# Bonus.net
KiCad netlist of a schematic drawn in EAGLE
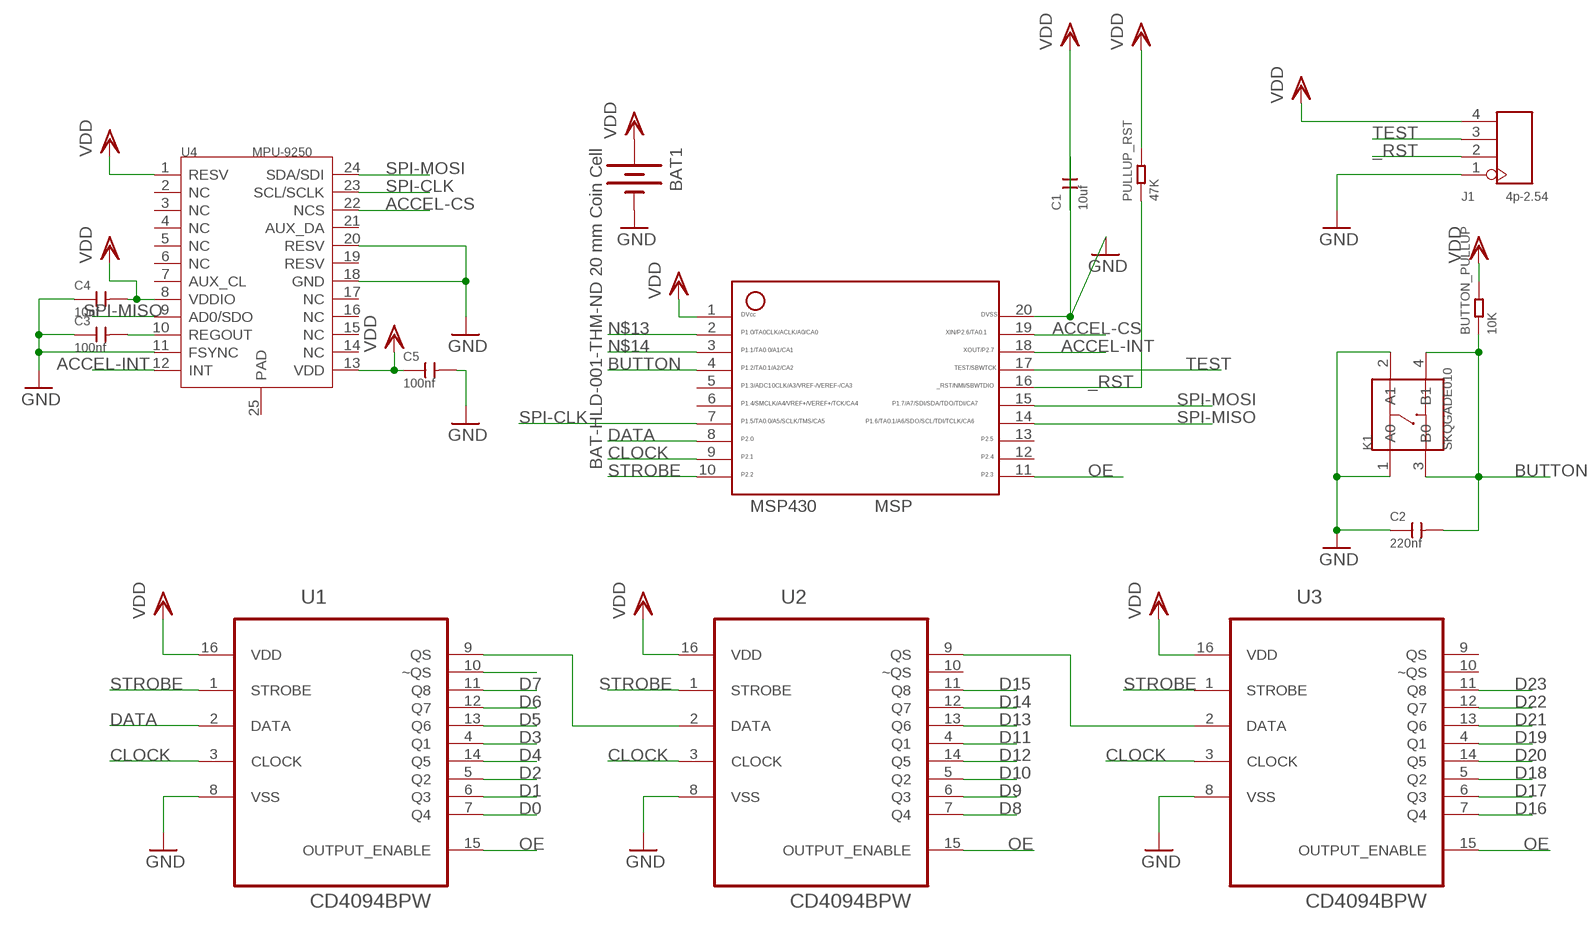
[diagram p0: schematic, sheet 1]
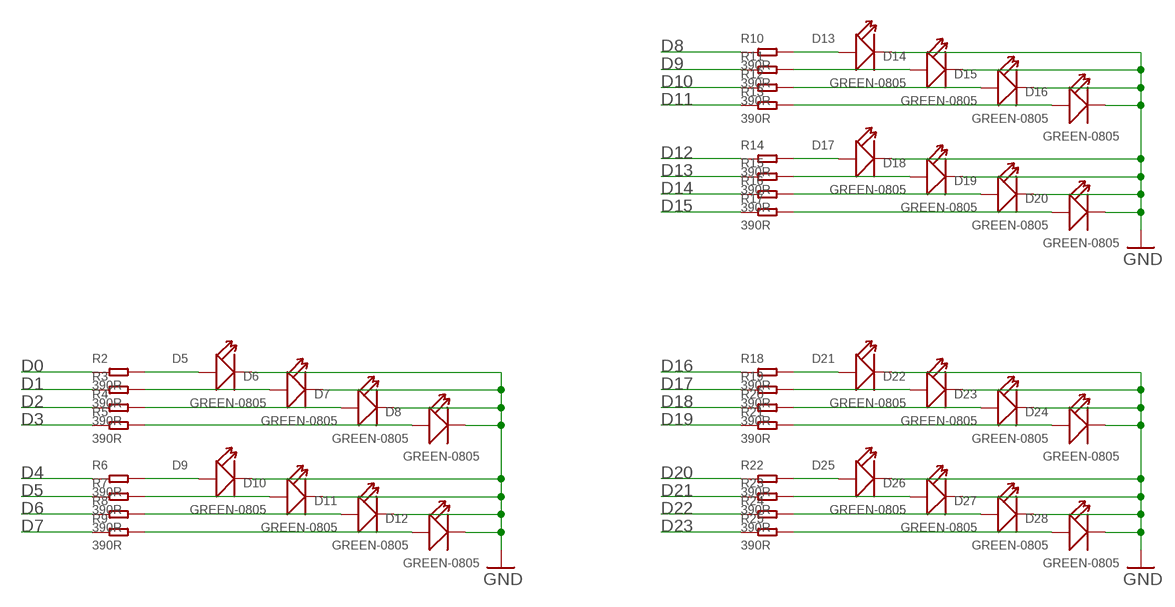
[diagram p1: schematic, sheet 2]

(export (version "E")
  (design (tool "Eeschema 10.0.6"))
  (components
    (comp (ref "D5")
      (value "GREEN-0805")
      (footprint "eagle-import:LED-0805")
      (fields (field (name "MPN") "17-215SYGC/S530-E2/TR8"))
      (libsource (lib "eagle-import") (part "SMD-LED-CLEAR-GREEN(0805)"))
    )
    (comp (ref "D6")
      (value "GREEN-0805")
      (footprint "eagle-import:LED-0805")
      (fields (field (name "MPN") "17-215SYGC/S530-E2/TR8"))
      (libsource (lib "eagle-import") (part "SMD-LED-CLEAR-GREEN(0805)"))
    )
    (comp (ref "D7")
      (value "GREEN-0805")
      (footprint "eagle-import:LED-0805")
      (fields (field (name "MPN") "17-215SYGC/S530-E2/TR8"))
      (libsource (lib "eagle-import") (part "SMD-LED-CLEAR-GREEN(0805)"))
    )
    (comp (ref "D8")
      (value "GREEN-0805")
      (footprint "eagle-import:LED-0805")
      (fields (field (name "MPN") "17-215SYGC/S530-E2/TR8"))
      (libsource (lib "eagle-import") (part "SMD-LED-CLEAR-GREEN(0805)"))
    )
    (comp (ref "D9")
      (value "GREEN-0805")
      (footprint "eagle-import:LED-0805")
      (fields (field (name "MPN") "17-215SYGC/S530-E2/TR8"))
      (libsource (lib "eagle-import") (part "SMD-LED-CLEAR-GREEN(0805)"))
    )
    (comp (ref "D10")
      (value "GREEN-0805")
      (footprint "eagle-import:LED-0805")
      (fields (field (name "MPN") "17-215SYGC/S530-E2/TR8"))
      (libsource (lib "eagle-import") (part "SMD-LED-CLEAR-GREEN(0805)"))
    )
    (comp (ref "D11")
      (value "GREEN-0805")
      (footprint "eagle-import:LED-0805")
      (fields (field (name "MPN") "17-215SYGC/S530-E2/TR8"))
      (libsource (lib "eagle-import") (part "SMD-LED-CLEAR-GREEN(0805)"))
    )
    (comp (ref "D12")
      (value "GREEN-0805")
      (footprint "eagle-import:LED-0805")
      (fields (field (name "MPN") "17-215SYGC/S530-E2/TR8"))
      (libsource (lib "eagle-import") (part "SMD-LED-CLEAR-GREEN(0805)"))
    )
    (comp (ref "D13")
      (value "GREEN-0805")
      (footprint "eagle-import:LED-0805")
      (fields (field (name "MPN") "17-215SYGC/S530-E2/TR8"))
      (libsource (lib "eagle-import") (part "SMD-LED-CLEAR-GREEN(0805)"))
    )
    (comp (ref "D14")
      (value "GREEN-0805")
      (footprint "eagle-import:LED-0805")
      (fields (field (name "MPN") "17-215SYGC/S530-E2/TR8"))
      (libsource (lib "eagle-import") (part "SMD-LED-CLEAR-GREEN(0805)"))
    )
    (comp (ref "D15")
      (value "GREEN-0805")
      (footprint "eagle-import:LED-0805")
      (fields (field (name "MPN") "17-215SYGC/S530-E2/TR8"))
      (libsource (lib "eagle-import") (part "SMD-LED-CLEAR-GREEN(0805)"))
    )
    (comp (ref "D16")
      (value "GREEN-0805")
      (footprint "eagle-import:LED-0805")
      (fields (field (name "MPN") "17-215SYGC/S530-E2/TR8"))
      (libsource (lib "eagle-import") (part "SMD-LED-CLEAR-GREEN(0805)"))
    )
    (comp (ref "D17")
      (value "GREEN-0805")
      (footprint "eagle-import:LED-0805")
      (fields (field (name "MPN") "17-215SYGC/S530-E2/TR8"))
      (libsource (lib "eagle-import") (part "SMD-LED-CLEAR-GREEN(0805)"))
    )
    (comp (ref "D18")
      (value "GREEN-0805")
      (footprint "eagle-import:LED-0805")
      (fields (field (name "MPN") "17-215SYGC/S530-E2/TR8"))
      (libsource (lib "eagle-import") (part "SMD-LED-CLEAR-GREEN(0805)"))
    )
    (comp (ref "D19")
      (value "GREEN-0805")
      (footprint "eagle-import:LED-0805")
      (fields (field (name "MPN") "17-215SYGC/S530-E2/TR8"))
      (libsource (lib "eagle-import") (part "SMD-LED-CLEAR-GREEN(0805)"))
    )
    (comp (ref "D20")
      (value "GREEN-0805")
      (footprint "eagle-import:LED-0805")
      (fields (field (name "MPN") "17-215SYGC/S530-E2/TR8"))
      (libsource (lib "eagle-import") (part "SMD-LED-CLEAR-GREEN(0805)"))
    )
    (comp (ref "D21")
      (value "GREEN-0805")
      (footprint "eagle-import:LED-0805")
      (fields (field (name "MPN") "17-215SYGC/S530-E2/TR8"))
      (libsource (lib "eagle-import") (part "SMD-LED-CLEAR-GREEN(0805)"))
    )
    (comp (ref "D22")
      (value "GREEN-0805")
      (footprint "eagle-import:LED-0805")
      (fields (field (name "MPN") "17-215SYGC/S530-E2/TR8"))
      (libsource (lib "eagle-import") (part "SMD-LED-CLEAR-GREEN(0805)"))
    )
    (comp (ref "D23")
      (value "GREEN-0805")
      (footprint "eagle-import:LED-0805")
      (fields (field (name "MPN") "17-215SYGC/S530-E2/TR8"))
      (libsource (lib "eagle-import") (part "SMD-LED-CLEAR-GREEN(0805)"))
    )
    (comp (ref "D24")
      (value "GREEN-0805")
      (footprint "eagle-import:LED-0805")
      (fields (field (name "MPN") "17-215SYGC/S530-E2/TR8"))
      (libsource (lib "eagle-import") (part "SMD-LED-CLEAR-GREEN(0805)"))
    )
    (comp (ref "D25")
      (value "GREEN-0805")
      (footprint "eagle-import:LED-0805")
      (fields (field (name "MPN") "17-215SYGC/S530-E2/TR8"))
      (libsource (lib "eagle-import") (part "SMD-LED-CLEAR-GREEN(0805)"))
    )
    (comp (ref "D26")
      (value "GREEN-0805")
      (footprint "eagle-import:LED-0805")
      (fields (field (name "MPN") "17-215SYGC/S530-E2/TR8"))
      (libsource (lib "eagle-import") (part "SMD-LED-CLEAR-GREEN(0805)"))
    )
    (comp (ref "D27")
      (value "GREEN-0805")
      (footprint "eagle-import:LED-0805")
      (fields (field (name "MPN") "17-215SYGC/S530-E2/TR8"))
      (libsource (lib "eagle-import") (part "SMD-LED-CLEAR-GREEN(0805)"))
    )
    (comp (ref "D28")
      (value "GREEN-0805")
      (footprint "eagle-import:LED-0805")
      (fields (field (name "MPN") "17-215SYGC/S530-E2/TR8"))
      (libsource (lib "eagle-import") (part "SMD-LED-CLEAR-GREEN(0805)"))
    )
    (comp (ref "R2")
      (value "390R")
      (footprint "eagle-import:R0603")
      (fields (field (name "MPN") "RC0603JR-07390RL"))
      (libsource (lib "eagle-import") (part "SMD-RES-390R-5%-1/10W(0603)"))
    )
    (comp (ref "R3")
      (value "390R")
      (footprint "eagle-import:R0603")
      (fields (field (name "MPN") "RC0603JR-07390RL"))
      (libsource (lib "eagle-import") (part "SMD-RES-390R-5%-1/10W(0603)"))
    )
    (comp (ref "R4")
      (value "390R")
      (footprint "eagle-import:R0603")
      (fields (field (name "MPN") "RC0603JR-07390RL"))
      (libsource (lib "eagle-import") (part "SMD-RES-390R-5%-1/10W(0603)"))
    )
    (comp (ref "R5")
      (value "390R")
      (footprint "eagle-import:R0603")
      (fields (field (name "MPN") "RC0603JR-07390RL"))
      (libsource (lib "eagle-import") (part "SMD-RES-390R-5%-1/10W(0603)"))
    )
    (comp (ref "R6")
      (value "390R")
      (footprint "eagle-import:R0603")
      (fields (field (name "MPN") "RC0603JR-07390RL"))
      (libsource (lib "eagle-import") (part "SMD-RES-390R-5%-1/10W(0603)"))
    )
    (comp (ref "R7")
      (value "390R")
      (footprint "eagle-import:R0603")
      (fields (field (name "MPN") "RC0603JR-07390RL"))
      (libsource (lib "eagle-import") (part "SMD-RES-390R-5%-1/10W(0603)"))
    )
    (comp (ref "R8")
      (value "390R")
      (footprint "eagle-import:R0603")
      (fields (field (name "MPN") "RC0603JR-07390RL"))
      (libsource (lib "eagle-import") (part "SMD-RES-390R-5%-1/10W(0603)"))
    )
    (comp (ref "R9")
      (value "390R")
      (footprint "eagle-import:R0603")
      (fields (field (name "MPN") "RC0603JR-07390RL"))
      (libsource (lib "eagle-import") (part "SMD-RES-390R-5%-1/10W(0603)"))
    )
    (comp (ref "R10")
      (value "390R")
      (footprint "eagle-import:R0603")
      (fields (field (name "MPN") "RC0603JR-07390RL"))
      (libsource (lib "eagle-import") (part "SMD-RES-390R-5%-1/10W(0603)"))
    )
    (comp (ref "R11")
      (value "390R")
      (footprint "eagle-import:R0603")
      (fields (field (name "MPN") "RC0603JR-07390RL"))
      (libsource (lib "eagle-import") (part "SMD-RES-390R-5%-1/10W(0603)"))
    )
    (comp (ref "R12")
      (value "390R")
      (footprint "eagle-import:R0603")
      (fields (field (name "MPN") "RC0603JR-07390RL"))
      (libsource (lib "eagle-import") (part "SMD-RES-390R-5%-1/10W(0603)"))
    )
    (comp (ref "R13")
      (value "390R")
      (footprint "eagle-import:R0603")
      (fields (field (name "MPN") "RC0603JR-07390RL"))
      (libsource (lib "eagle-import") (part "SMD-RES-390R-5%-1/10W(0603)"))
    )
    (comp (ref "R14")
      (value "390R")
      (footprint "eagle-import:R0603")
      (fields (field (name "MPN") "RC0603JR-07390RL"))
      (libsource (lib "eagle-import") (part "SMD-RES-390R-5%-1/10W(0603)"))
    )
    (comp (ref "R15")
      (value "390R")
      (footprint "eagle-import:R0603")
      (fields (field (name "MPN") "RC0603JR-07390RL"))
      (libsource (lib "eagle-import") (part "SMD-RES-390R-5%-1/10W(0603)"))
    )
    (comp (ref "R16")
      (value "390R")
      (footprint "eagle-import:R0603")
      (fields (field (name "MPN") "RC0603JR-07390RL"))
      (libsource (lib "eagle-import") (part "SMD-RES-390R-5%-1/10W(0603)"))
    )
    (comp (ref "R17")
      (value "390R")
      (footprint "eagle-import:R0603")
      (fields (field (name "MPN") "RC0603JR-07390RL"))
      (libsource (lib "eagle-import") (part "SMD-RES-390R-5%-1/10W(0603)"))
    )
    (comp (ref "R18")
      (value "390R")
      (footprint "eagle-import:R0603")
      (fields (field (name "MPN") "RC0603JR-07390RL"))
      (libsource (lib "eagle-import") (part "SMD-RES-390R-5%-1/10W(0603)"))
    )
    (comp (ref "R19")
      (value "390R")
      (footprint "eagle-import:R0603")
      (fields (field (name "MPN") "RC0603JR-07390RL"))
      (libsource (lib "eagle-import") (part "SMD-RES-390R-5%-1/10W(0603)"))
    )
    (comp (ref "R20")
      (value "390R")
      (footprint "eagle-import:R0603")
      (fields (field (name "MPN") "RC0603JR-07390RL"))
      (libsource (lib "eagle-import") (part "SMD-RES-390R-5%-1/10W(0603)"))
    )
    (comp (ref "R21")
      (value "390R")
      (footprint "eagle-import:R0603")
      (fields (field (name "MPN") "RC0603JR-07390RL"))
      (libsource (lib "eagle-import") (part "SMD-RES-390R-5%-1/10W(0603)"))
    )
    (comp (ref "R22")
      (value "390R")
      (footprint "eagle-import:R0603")
      (fields (field (name "MPN") "RC0603JR-07390RL"))
      (libsource (lib "eagle-import") (part "SMD-RES-390R-5%-1/10W(0603)"))
    )
    (comp (ref "R23")
      (value "390R")
      (footprint "eagle-import:R0603")
      (fields (field (name "MPN") "RC0603JR-07390RL"))
      (libsource (lib "eagle-import") (part "SMD-RES-390R-5%-1/10W(0603)"))
    )
    (comp (ref "R24")
      (value "390R")
      (footprint "eagle-import:R0603")
      (fields (field (name "MPN") "RC0603JR-07390RL"))
      (libsource (lib "eagle-import") (part "SMD-RES-390R-5%-1/10W(0603)"))
    )
    (comp (ref "R25")
      (value "390R")
      (footprint "eagle-import:R0603")
      (fields (field (name "MPN") "RC0603JR-07390RL"))
      (libsource (lib "eagle-import") (part "SMD-RES-390R-5%-1/10W(0603)"))
    )
    (comp (ref "BAT1")
      (value "BAT-HLD-001-THM-ND 20 mm Coin Cell")
      (footprint "eagle-import:BATTCON_20MM_PTH_COMPACT")
      (libsource (lib "eagle-import") (part "BATTERYFOB"))
    )
    (comp (ref "BUTTON_PULLUP")
      (value "10K")
      (footprint "eagle-import:R0603")
      (fields (field (name "MPN") "RC0603FR-0710KL"))
      (libsource (lib "eagle-import") (part "SMD-RES-10K-1%-1/10W(0603)"))
    )
    (comp (ref "C1")
      (value "10uf")
      (footprint "eagle-import:C0805")
      (fields (field (name "MPN") "CC0805ZKY5V6BB106"))
      (libsource (lib "eagle-import") (part "CERAMIC-10UF-10V-(-20%～+80%)-Y5V(0805)"))
    )
    (comp (ref "C2")
      (value "220nf")
      (footprint "eagle-import:C0603")
      (fields (field (name "MPN") "CC0603KRX7R8BB224"))
      (libsource (lib "eagle-import") (part "CERAMIC-220NF-25V-10%-X7R(0603)"))
    )
    (comp (ref "C3")
      (value "100nf")
      (footprint "eagle-import:C0402")
      (fields (field (name "MPN") "CC0402KRX7R8BB104"))
      (libsource (lib "eagle-import") (part "CERAMIC-100NF-25V-10%-X7R(0402)"))
    )
    (comp (ref "C4")
      (value "10nf")
      (footprint "eagle-import:C0402")
      (fields (field (name "MPN") "CC0402KRX7R9BB103"))
      (libsource (lib "eagle-import") (part "CERAMIC-10NF-50V-10%-X7R(0402)"))
    )
    (comp (ref "C5")
      (value "100nf")
      (footprint "eagle-import:C0402")
      (fields (field (name "MPN") "CC0402KRX7R8BB104"))
      (libsource (lib "eagle-import") (part "CERAMIC-100NF-25V-10%-X7R(0402)"))
    )
    (comp (ref "J1")
      (value "4p-2.54")
      (footprint "eagle-import:H4-2.54")
      (fields (field (name "MPN") "F185-1104A1BSYA1"))
      (libsource (lib "eagle-import") (part "DIP-BLACK-FEMALE-HEADER-VERT(4P-2.54)"))
    )
    (comp (ref "K1")
      (value "SKQGADE010")
      (footprint "eagle-import:SW4-SMD-5.2X5.2X1.5MM")
      (libsource (lib "eagle-import") (part "SMD-BUTTON(4P-5.2X5.2X1.5MM-SKQGADE010)-SKQGADE010"))
    )
    (comp (ref "MSP430")
      (value "MSP")
      (footprint "eagle-import:20_PIN")
      (libsource (lib "eagle-import") (part "MSP430"))
    )
    (comp (ref "PULLUP_RST")
      (value "47K")
      (footprint "eagle-import:R0603")
      (fields (field (name "MPN") "RC0603JR-0747KL"))
      (libsource (lib "eagle-import") (part "SMD-RES-47K-5%-1/10W(0603)"))
    )
    (comp (ref "U1")
      (value "CD4094BPW")
      (footprint "eagle-import:SOP65P640X120-16N")
      (libsource (lib "eagle-import") (part "CD4094BPW"))
    )
    (comp (ref "U2")
      (value "CD4094BPW")
      (footprint "eagle-import:SOP65P640X120-16N")
      (libsource (lib "eagle-import") (part "CD4094BPW"))
    )
    (comp (ref "U3")
      (value "CD4094BPW")
      (footprint "eagle-import:SOP65P640X120-16N")
      (libsource (lib "eagle-import") (part "CD4094BPW"))
    )
    (comp (ref "U4")
      (value "MPU-9250")
      (footprint "eagle-import:QFN24G-0.4-3X3MM")
      (libsource (lib "eagle-import") (part "MOTION/POSITION-MPU-9250(QFN24)"))
    )
  )
  (nets
    (net (code "1") (name "ACCEL-CS") (class "Default")
      (node (ref "MSP430") (pin "19") (pinfunction "19_19") (pintype "bidirectional"))
      (node (ref "U4") (pin "22") (pinfunction "NCS_22") (pintype "bidirectional"))
    )
    (net (code "2") (name "ACCEL-INT") (class "Default")
      (node (ref "MSP430") (pin "18") (pinfunction "18_18") (pintype "bidirectional"))
      (node (ref "U4") (pin "12") (pinfunction "INT_12") (pintype "bidirectional"))
    )
    (net (code "3") (name "BUTTON") (class "Default")
      (node (ref "BUTTON_PULLUP") (pin "1") (pinfunction "1_1") (pintype "passive"))
      (node (ref "C2") (pin "2") (pinfunction "2_2") (pintype "passive"))
      (node (ref "K1") (pin "3") (pinfunction "B0_3") (pintype "bidirectional"))
      (node (ref "K1") (pin "4") (pinfunction "B1_4") (pintype "bidirectional"))
      (node (ref "MSP430") (pin "4") (pinfunction "4_4") (pintype "bidirectional"))
    )
    (net (code "4") (name "CLOCK") (class "Default")
      (node (ref "MSP430") (pin "9") (pinfunction "9_9") (pintype "bidirectional"))
      (node (ref "U1") (pin "3") (pinfunction "CLOCK_3") (pintype "input"))
      (node (ref "U2") (pin "3") (pinfunction "CLOCK_3") (pintype "input"))
      (node (ref "U3") (pin "3") (pinfunction "CLOCK_3") (pintype "input"))
    )
    (net (code "5") (name "D0") (class "Default")
      (node (ref "R2") (pin "1") (pinfunction "1_1") (pintype "passive"))
      (node (ref "U1") (pin "7") (pinfunction "Q4_7") (pintype "output"))
    )
    (net (code "6") (name "D1") (class "Default")
      (node (ref "R3") (pin "1") (pinfunction "1_1") (pintype "passive"))
      (node (ref "U1") (pin "6") (pinfunction "Q3_6") (pintype "output"))
    )
    (net (code "7") (name "D2") (class "Default")
      (node (ref "R4") (pin "1") (pinfunction "1_1") (pintype "passive"))
      (node (ref "U1") (pin "5") (pinfunction "Q2_5") (pintype "output"))
    )
    (net (code "8") (name "D3") (class "Default")
      (node (ref "R5") (pin "1") (pinfunction "1_1") (pintype "passive"))
      (node (ref "U1") (pin "4") (pinfunction "Q1_4") (pintype "output"))
    )
    (net (code "9") (name "D4") (class "Default")
      (node (ref "R6") (pin "1") (pinfunction "1_1") (pintype "passive"))
      (node (ref "U1") (pin "14") (pinfunction "Q5_14") (pintype "output"))
    )
    (net (code "10") (name "D5") (class "Default")
      (node (ref "R7") (pin "1") (pinfunction "1_1") (pintype "passive"))
      (node (ref "U1") (pin "13") (pinfunction "Q6_13") (pintype "output"))
    )
    (net (code "11") (name "D6") (class "Default")
      (node (ref "R8") (pin "1") (pinfunction "1_1") (pintype "passive"))
      (node (ref "U1") (pin "12") (pinfunction "Q7_12") (pintype "output"))
    )
    (net (code "12") (name "D7") (class "Default")
      (node (ref "R9") (pin "1") (pinfunction "1_1") (pintype "passive"))
      (node (ref "U1") (pin "11") (pinfunction "Q8_11") (pintype "output"))
    )
    (net (code "13") (name "D8") (class "Default")
      (node (ref "R10") (pin "1") (pinfunction "1_1") (pintype "passive"))
      (node (ref "U2") (pin "7") (pinfunction "Q4_7") (pintype "output"))
    )
    (net (code "14") (name "D9") (class "Default")
      (node (ref "R11") (pin "1") (pinfunction "1_1") (pintype "passive"))
      (node (ref "U2") (pin "6") (pinfunction "Q3_6") (pintype "output"))
    )
    (net (code "15") (name "D10") (class "Default")
      (node (ref "R12") (pin "1") (pinfunction "1_1") (pintype "passive"))
      (node (ref "U2") (pin "5") (pinfunction "Q2_5") (pintype "output"))
    )
    (net (code "16") (name "D11") (class "Default")
      (node (ref "R13") (pin "1") (pinfunction "1_1") (pintype "passive"))
      (node (ref "U2") (pin "4") (pinfunction "Q1_4") (pintype "output"))
    )
    (net (code "17") (name "D12") (class "Default")
      (node (ref "R14") (pin "1") (pinfunction "1_1") (pintype "passive"))
      (node (ref "U2") (pin "14") (pinfunction "Q5_14") (pintype "output"))
    )
    (net (code "18") (name "D13") (class "Default")
      (node (ref "R15") (pin "1") (pinfunction "1_1") (pintype "passive"))
      (node (ref "U2") (pin "13") (pinfunction "Q6_13") (pintype "output"))
    )
    (net (code "19") (name "D14") (class "Default")
      (node (ref "R16") (pin "1") (pinfunction "1_1") (pintype "passive"))
      (node (ref "U2") (pin "12") (pinfunction "Q7_12") (pintype "output"))
    )
    (net (code "20") (name "D15") (class "Default")
      (node (ref "R17") (pin "1") (pinfunction "1_1") (pintype "passive"))
      (node (ref "U2") (pin "11") (pinfunction "Q8_11") (pintype "output"))
    )
    (net (code "21") (name "D16") (class "Default")
      (node (ref "R18") (pin "1") (pinfunction "1_1") (pintype "passive"))
      (node (ref "U3") (pin "7") (pinfunction "Q4_7") (pintype "output"))
    )
    (net (code "22") (name "D17") (class "Default")
      (node (ref "R19") (pin "1") (pinfunction "1_1") (pintype "passive"))
      (node (ref "U3") (pin "6") (pinfunction "Q3_6") (pintype "output"))
    )
    (net (code "23") (name "D18") (class "Default")
      (node (ref "R20") (pin "1") (pinfunction "1_1") (pintype "passive"))
      (node (ref "U3") (pin "5") (pinfunction "Q2_5") (pintype "output"))
    )
    (net (code "24") (name "D19") (class "Default")
      (node (ref "R21") (pin "1") (pinfunction "1_1") (pintype "passive"))
      (node (ref "U3") (pin "4") (pinfunction "Q1_4") (pintype "output"))
    )
    (net (code "25") (name "D20") (class "Default")
      (node (ref "R22") (pin "1") (pinfunction "1_1") (pintype "passive"))
      (node (ref "U3") (pin "14") (pinfunction "Q5_14") (pintype "output"))
    )
    (net (code "26") (name "D21") (class "Default")
      (node (ref "R23") (pin "1") (pinfunction "1_1") (pintype "passive"))
      (node (ref "U3") (pin "13") (pinfunction "Q6_13") (pintype "output"))
    )
    (net (code "27") (name "D22") (class "Default")
      (node (ref "R24") (pin "1") (pinfunction "1_1") (pintype "passive"))
      (node (ref "U3") (pin "12") (pinfunction "Q7_12") (pintype "output"))
    )
    (net (code "28") (name "D23") (class "Default")
      (node (ref "R25") (pin "1") (pinfunction "1_1") (pintype "passive"))
      (node (ref "U3") (pin "11") (pinfunction "Q8_11") (pintype "output"))
    )
    (net (code "29") (name "DATA") (class "Default")
      (node (ref "MSP430") (pin "8") (pinfunction "8_8") (pintype "bidirectional"))
      (node (ref "U1") (pin "2") (pinfunction "DATA_2") (pintype "input"))
    )
    (net (code "30") (name "GND") (class "Default")
      (node (ref "BAT1") (pin "2") (pinfunction "-_2") (pintype "power_in"))
      (node (ref "C1") (pin "2") (pinfunction "2_2") (pintype "passive"))
      (node (ref "C2") (pin "1") (pinfunction "1_1") (pintype "passive"))
      (node (ref "C3") (pin "1") (pinfunction "1_1") (pintype "passive"))
      (node (ref "C4") (pin "1") (pinfunction "1_1") (pintype "passive"))
      (node (ref "C5") (pin "2") (pinfunction "2_2") (pintype "passive"))
      (node (ref "D10") (pin "-") (pinfunction "-_-") (pintype "passive"))
      (node (ref "D11") (pin "-") (pinfunction "-_-") (pintype "passive"))
      (node (ref "D12") (pin "-") (pinfunction "-_-") (pintype "passive"))
      (node (ref "D13") (pin "-") (pinfunction "-_-") (pintype "passive"))
      (node (ref "D14") (pin "-") (pinfunction "-_-") (pintype "passive"))
      (node (ref "D15") (pin "-") (pinfunction "-_-") (pintype "passive"))
      (node (ref "D16") (pin "-") (pinfunction "-_-") (pintype "passive"))
      (node (ref "D17") (pin "-") (pinfunction "-_-") (pintype "passive"))
      (node (ref "D18") (pin "-") (pinfunction "-_-") (pintype "passive"))
      (node (ref "D19") (pin "-") (pinfunction "-_-") (pintype "passive"))
      (node (ref "D20") (pin "-") (pinfunction "-_-") (pintype "passive"))
      (node (ref "D21") (pin "-") (pinfunction "-_-") (pintype "passive"))
      (node (ref "D22") (pin "-") (pinfunction "-_-") (pintype "passive"))
      (node (ref "D23") (pin "-") (pinfunction "-_-") (pintype "passive"))
      (node (ref "D24") (pin "-") (pinfunction "-_-") (pintype "passive"))
      (node (ref "D25") (pin "-") (pinfunction "-_-") (pintype "passive"))
      (node (ref "D26") (pin "-") (pinfunction "-_-") (pintype "passive"))
      (node (ref "D27") (pin "-") (pinfunction "-_-") (pintype "passive"))
      (node (ref "D28") (pin "-") (pinfunction "-_-") (pintype "passive"))
      (node (ref "D5") (pin "-") (pinfunction "-_-") (pintype "passive"))
      (node (ref "D6") (pin "-") (pinfunction "-_-") (pintype "passive"))
      (node (ref "D7") (pin "-") (pinfunction "-_-") (pintype "passive"))
      (node (ref "D8") (pin "-") (pinfunction "-_-") (pintype "passive"))
      (node (ref "D9") (pin "-") (pinfunction "-_-") (pintype "passive"))
      (node (ref "J1") (pin "1") (pinfunction "P$1_1") (pintype "bidirectional"))
      (node (ref "K1") (pin "1") (pinfunction "A0_1") (pintype "bidirectional"))
      (node (ref "K1") (pin "2") (pinfunction "A1_2") (pintype "bidirectional"))
      (node (ref "MSP430") (pin "20") (pinfunction "20_20") (pintype "bidirectional"))
      (node (ref "U1") (pin "8") (pinfunction "VSS_8") (pintype "power_in"))
      (node (ref "U2") (pin "8") (pinfunction "VSS_8") (pintype "power_in"))
      (node (ref "U3") (pin "8") (pinfunction "VSS_8") (pintype "power_in"))
      (node (ref "U4") (pin "11") (pinfunction "FSYNC_11") (pintype "bidirectional"))
      (node (ref "U4") (pin "18") (pinfunction "GND_18") (pintype "bidirectional"))
      (node (ref "U4") (pin "20") (pinfunction "RESV_20") (pintype "bidirectional"))
    )
    (net (code "31") (name "N$13") (class "Default")
      (node (ref "MSP430") (pin "2") (pinfunction "2_2") (pintype "bidirectional"))
    )
    (net (code "32") (name "N$14") (class "Default")
      (node (ref "MSP430") (pin "3") (pinfunction "3_3") (pintype "bidirectional"))
    )
    (net (code "33") (name "Net-(D5-Pad+)") (class "Default")
      (node (ref "D5") (pin "+") (pinfunction "+_+") (pintype "passive"))
      (node (ref "R2") (pin "2") (pinfunction "2_2") (pintype "passive"))
    )
    (net (code "34") (name "Net-(D6-Pad+)") (class "Default")
      (node (ref "D6") (pin "+") (pinfunction "+_+") (pintype "passive"))
      (node (ref "R3") (pin "2") (pinfunction "2_2") (pintype "passive"))
    )
    (net (code "35") (name "Net-(D7-Pad+)") (class "Default")
      (node (ref "D7") (pin "+") (pinfunction "+_+") (pintype "passive"))
      (node (ref "R4") (pin "2") (pinfunction "2_2") (pintype "passive"))
    )
    (net (code "36") (name "Net-(D8-Pad+)") (class "Default")
      (node (ref "D8") (pin "+") (pinfunction "+_+") (pintype "passive"))
      (node (ref "R5") (pin "2") (pinfunction "2_2") (pintype "passive"))
    )
    (net (code "37") (name "Net-(D9-Pad+)") (class "Default")
      (node (ref "D9") (pin "+") (pinfunction "+_+") (pintype "passive"))
      (node (ref "R6") (pin "2") (pinfunction "2_2") (pintype "passive"))
    )
    (net (code "38") (name "Net-(D10-Pad+)") (class "Default")
      (node (ref "D10") (pin "+") (pinfunction "+_+") (pintype "passive"))
      (node (ref "R7") (pin "2") (pinfunction "2_2") (pintype "passive"))
    )
    (net (code "39") (name "Net-(D11-Pad+)") (class "Default")
      (node (ref "D11") (pin "+") (pinfunction "+_+") (pintype "passive"))
      (node (ref "R8") (pin "2") (pinfunction "2_2") (pintype "passive"))
    )
    (net (code "40") (name "Net-(D12-Pad+)") (class "Default")
      (node (ref "D12") (pin "+") (pinfunction "+_+") (pintype "passive"))
      (node (ref "R9") (pin "2") (pinfunction "2_2") (pintype "passive"))
    )
    (net (code "41") (name "Net-(D13-Pad+)") (class "Default")
      (node (ref "D13") (pin "+") (pinfunction "+_+") (pintype "passive"))
      (node (ref "R10") (pin "2") (pinfunction "2_2") (pintype "passive"))
    )
    (net (code "42") (name "Net-(D14-Pad+)") (class "Default")
      (node (ref "D14") (pin "+") (pinfunction "+_+") (pintype "passive"))
      (node (ref "R11") (pin "2") (pinfunction "2_2") (pintype "passive"))
    )
    (net (code "43") (name "Net-(D15-Pad+)") (class "Default")
      (node (ref "D15") (pin "+") (pinfunction "+_+") (pintype "passive"))
      (node (ref "R12") (pin "2") (pinfunction "2_2") (pintype "passive"))
    )
    (net (code "44") (name "Net-(D16-Pad+)") (class "Default")
      (node (ref "D16") (pin "+") (pinfunction "+_+") (pintype "passive"))
      (node (ref "R13") (pin "2") (pinfunction "2_2") (pintype "passive"))
    )
    (net (code "45") (name "Net-(D17-Pad+)") (class "Default")
      (node (ref "D17") (pin "+") (pinfunction "+_+") (pintype "passive"))
      (node (ref "R14") (pin "2") (pinfunction "2_2") (pintype "passive"))
    )
    (net (code "46") (name "Net-(D18-Pad+)") (class "Default")
      (node (ref "D18") (pin "+") (pinfunction "+_+") (pintype "passive"))
      (node (ref "R15") (pin "2") (pinfunction "2_2") (pintype "passive"))
    )
    (net (code "47") (name "Net-(D19-Pad+)") (class "Default")
      (node (ref "D19") (pin "+") (pinfunction "+_+") (pintype "passive"))
      (node (ref "R16") (pin "2") (pinfunction "2_2") (pintype "passive"))
    )
    (net (code "48") (name "Net-(D20-Pad+)") (class "Default")
      (node (ref "D20") (pin "+") (pinfunction "+_+") (pintype "passive"))
      (node (ref "R17") (pin "2") (pinfunction "2_2") (pintype "passive"))
    )
    (net (code "49") (name "Net-(D21-Pad+)") (class "Default")
      (node (ref "D21") (pin "+") (pinfunction "+_+") (pintype "passive"))
      (node (ref "R18") (pin "2") (pinfunction "2_2") (pintype "passive"))
    )
    (net (code "50") (name "Net-(D22-Pad+)") (class "Default")
      (node (ref "D22") (pin "+") (pinfunction "+_+") (pintype "passive"))
      (node (ref "R19") (pin "2") (pinfunction "2_2") (pintype "passive"))
    )
    (net (code "51") (name "Net-(D23-Pad+)") (class "Default")
      (node (ref "D23") (pin "+") (pinfunction "+_+") (pintype "passive"))
      (node (ref "R20") (pin "2") (pinfunction "2_2") (pintype "passive"))
    )
    (net (code "52") (name "Net-(D24-Pad+)") (class "Default")
      (node (ref "D24") (pin "+") (pinfunction "+_+") (pintype "passive"))
      (node (ref "R21") (pin "2") (pinfunction "2_2") (pintype "passive"))
    )
    (net (code "53") (name "Net-(D25-Pad+)") (class "Default")
      (node (ref "D25") (pin "+") (pinfunction "+_+") (pintype "passive"))
      (node (ref "R22") (pin "2") (pinfunction "2_2") (pintype "passive"))
    )
    (net (code "54") (name "Net-(D26-Pad+)") (class "Default")
      (node (ref "D26") (pin "+") (pinfunction "+_+") (pintype "passive"))
      (node (ref "R23") (pin "2") (pinfunction "2_2") (pintype "passive"))
    )
    (net (code "55") (name "Net-(D27-Pad+)") (class "Default")
      (node (ref "D27") (pin "+") (pinfunction "+_+") (pintype "passive"))
      (node (ref "R24") (pin "2") (pinfunction "2_2") (pintype "passive"))
    )
    (net (code "56") (name "Net-(D28-Pad+)") (class "Default")
      (node (ref "D28") (pin "+") (pinfunction "+_+") (pintype "passive"))
      (node (ref "R25") (pin "2") (pinfunction "2_2") (pintype "passive"))
    )
    (net (code "57") (name "Net-(U1-QS)") (class "Default")
      (node (ref "U1") (pin "9") (pinfunction "QS_9") (pintype "output"))
      (node (ref "U2") (pin "2") (pinfunction "DATA_2") (pintype "input"))
    )
    (net (code "58") (name "Net-(U2-QS)") (class "Default")
      (node (ref "U2") (pin "9") (pinfunction "QS_9") (pintype "output"))
      (node (ref "U3") (pin "2") (pinfunction "DATA_2") (pintype "input"))
    )
    (net (code "59") (name "Net-(U4-REGOUT)") (class "Default")
      (node (ref "C3") (pin "2") (pinfunction "2_2") (pintype "passive"))
      (node (ref "U4") (pin "10") (pinfunction "REGOUT_10") (pintype "bidirectional"))
    )
    (net (code "60") (name "OE") (class "Default")
      (node (ref "MSP430") (pin "11") (pinfunction "11_11") (pintype "bidirectional"))
      (node (ref "U1") (pin "15") (pinfunction "OUTPUT_ENABLE_15") (pintype "output"))
      (node (ref "U2") (pin "15") (pinfunction "OUTPUT_ENABLE_15") (pintype "output"))
      (node (ref "U3") (pin "15") (pinfunction "OUTPUT_ENABLE_15") (pintype "output"))
    )
    (net (code "61") (name "SPI-CLK") (class "Default")
      (node (ref "MSP430") (pin "7") (pinfunction "7_7") (pintype "bidirectional"))
      (node (ref "U4") (pin "23") (pinfunction "SCL/SCLK_23") (pintype "bidirectional"))
    )
    (net (code "62") (name "SPI-MISO") (class "Default")
      (node (ref "MSP430") (pin "14") (pinfunction "14_14") (pintype "bidirectional"))
      (node (ref "U4") (pin "9") (pinfunction "AD0/SDO_9") (pintype "bidirectional"))
    )
    (net (code "63") (name "SPI-MOSI") (class "Default")
      (node (ref "MSP430") (pin "15") (pinfunction "15_15") (pintype "bidirectional"))
      (node (ref "U4") (pin "24") (pinfunction "SDA/SDI_24") (pintype "bidirectional"))
    )
    (net (code "64") (name "STROBE") (class "Default")
      (node (ref "MSP430") (pin "10") (pinfunction "10_10") (pintype "bidirectional"))
      (node (ref "U1") (pin "1") (pinfunction "STROBE_1") (pintype "input"))
      (node (ref "U2") (pin "1") (pinfunction "STROBE_1") (pintype "input"))
      (node (ref "U3") (pin "1") (pinfunction "STROBE_1") (pintype "input"))
    )
    (net (code "65") (name "TEST") (class "Default")
      (node (ref "J1") (pin "3") (pinfunction "P$3_3") (pintype "bidirectional"))
      (node (ref "MSP430") (pin "17") (pinfunction "17_17") (pintype "bidirectional"))
    )
    (net (code "66") (name "VDD") (class "Default")
      (node (ref "BAT1") (pin "1") (pinfunction "+_1") (pintype "power_in"))
      (node (ref "BAT1") (pin "3") (pinfunction "+_3") (pintype "power_in"))
      (node (ref "BAT1") (pin "4") (pinfunction "+_4") (pintype "power_in"))
      (node (ref "BAT1") (pin "5") (pinfunction "+_5") (pintype "power_in"))
      (node (ref "BUTTON_PULLUP") (pin "2") (pinfunction "2_2") (pintype "passive"))
      (node (ref "C1") (pin "1") (pinfunction "1_1") (pintype "passive"))
      (node (ref "C4") (pin "2") (pinfunction "2_2") (pintype "passive"))
      (node (ref "C5") (pin "1") (pinfunction "1_1") (pintype "passive"))
      (node (ref "J1") (pin "4") (pinfunction "P$4_4") (pintype "bidirectional"))
      (node (ref "MSP430") (pin "1") (pinfunction "1_1") (pintype "bidirectional"))
      (node (ref "PULLUP_RST") (pin "2") (pinfunction "2_2") (pintype "passive"))
      (node (ref "U1") (pin "16") (pinfunction "VDD_16") (pintype "power_in"))
      (node (ref "U2") (pin "16") (pinfunction "VDD_16") (pintype "power_in"))
      (node (ref "U3") (pin "16") (pinfunction "VDD_16") (pintype "power_in"))
      (node (ref "U4") (pin "1") (pinfunction "RESV_1") (pintype "bidirectional"))
      (node (ref "U4") (pin "13") (pinfunction "VDD_13") (pintype "bidirectional"))
      (node (ref "U4") (pin "8") (pinfunction "VDDIO_8") (pintype "bidirectional"))
    )
    (net (code "67") (name "_RST") (class "Default")
      (node (ref "J1") (pin "2") (pinfunction "P$2_2") (pintype "bidirectional"))
      (node (ref "MSP430") (pin "16") (pinfunction "16_16") (pintype "bidirectional"))
      (node (ref "PULLUP_RST") (pin "1") (pinfunction "1_1") (pintype "passive"))
    )
    (net (code "68") (name "unconnected-(MSP430-Pad5)") (class "Default")
      (node (ref "MSP430") (pin "5") (pinfunction "5_5") (pintype "bidirectional"))
    )
    (net (code "69") (name "unconnected-(MSP430-Pad6)") (class "Default")
      (node (ref "MSP430") (pin "6") (pinfunction "6_6") (pintype "bidirectional"))
    )
    (net (code "70") (name "unconnected-(MSP430-Pad12)") (class "Default")
      (node (ref "MSP430") (pin "12") (pinfunction "12_12") (pintype "bidirectional"))
    )
    (net (code "71") (name "unconnected-(MSP430-Pad13)") (class "Default")
      (node (ref "MSP430") (pin "13") (pinfunction "13_13") (pintype "bidirectional"))
    )
    (net (code "72") (name "unconnected-(U1-~{QS}-Pad10)") (class "Default")
      (node (ref "U1") (pin "10") (pinfunction "~{QS}_10") (pintype "output"))
    )
    (net (code "73") (name "unconnected-(U2-~{QS}-Pad10)") (class "Default")
      (node (ref "U2") (pin "10") (pinfunction "~{QS}_10") (pintype "output"))
    )
    (net (code "74") (name "unconnected-(U3-QS-Pad9)") (class "Default")
      (node (ref "U3") (pin "9") (pinfunction "QS_9") (pintype "output"))
    )
    (net (code "75") (name "unconnected-(U3-~{QS}-Pad10)") (class "Default")
      (node (ref "U3") (pin "10") (pinfunction "~{QS}_10") (pintype "output"))
    )
    (net (code "76") (name "unconnected-(U4-AUX_CL-Pad7)") (class "Default")
      (node (ref "U4") (pin "7") (pinfunction "AUX_CL_7") (pintype "bidirectional"))
    )
    (net (code "77") (name "unconnected-(U4-AUX_DA-Pad21)") (class "Default")
      (node (ref "U4") (pin "21") (pinfunction "AUX_DA_21") (pintype "bidirectional"))
    )
    (net (code "78") (name "unconnected-(U4-NC-Pad2)") (class "Default")
      (node (ref "U4") (pin "2") (pinfunction "NC_2") (pintype "bidirectional"))
    )
    (net (code "79") (name "unconnected-(U4-NC-Pad3)") (class "Default")
      (node (ref "U4") (pin "3") (pinfunction "NC_3") (pintype "bidirectional"))
    )
    (net (code "80") (name "unconnected-(U4-NC-Pad4)") (class "Default")
      (node (ref "U4") (pin "4") (pinfunction "NC_4") (pintype "bidirectional"))
    )
    (net (code "81") (name "unconnected-(U4-NC-Pad5)") (class "Default")
      (node (ref "U4") (pin "5") (pinfunction "NC_5") (pintype "bidirectional"))
    )
    (net (code "82") (name "unconnected-(U4-NC-Pad6)") (class "Default")
      (node (ref "U4") (pin "6") (pinfunction "NC_6") (pintype "bidirectional"))
    )
    (net (code "83") (name "unconnected-(U4-NC-Pad14)") (class "Default")
      (node (ref "U4") (pin "14") (pinfunction "NC_14") (pintype "bidirectional"))
    )
    (net (code "84") (name "unconnected-(U4-NC-Pad15)") (class "Default")
      (node (ref "U4") (pin "15") (pinfunction "NC_15") (pintype "bidirectional"))
    )
    (net (code "85") (name "unconnected-(U4-NC-Pad16)") (class "Default")
      (node (ref "U4") (pin "16") (pinfunction "NC_16") (pintype "bidirectional"))
    )
    (net (code "86") (name "unconnected-(U4-NC-Pad17)") (class "Default")
      (node (ref "U4") (pin "17") (pinfunction "NC_17") (pintype "bidirectional"))
    )
    (net (code "87") (name "unconnected-(U4-PAD-Pad25)") (class "Default")
      (node (ref "U4") (pin "25") (pinfunction "PAD_25") (pintype "bidirectional"))
    )
    (net (code "88") (name "unconnected-(U4-RESV-Pad19)") (class "Default")
      (node (ref "U4") (pin "19") (pinfunction "RESV_19") (pintype "bidirectional"))
    )
  )
)
